# 1_POWER.net
KiCad netlist of a schematic drawn in Altium Designer
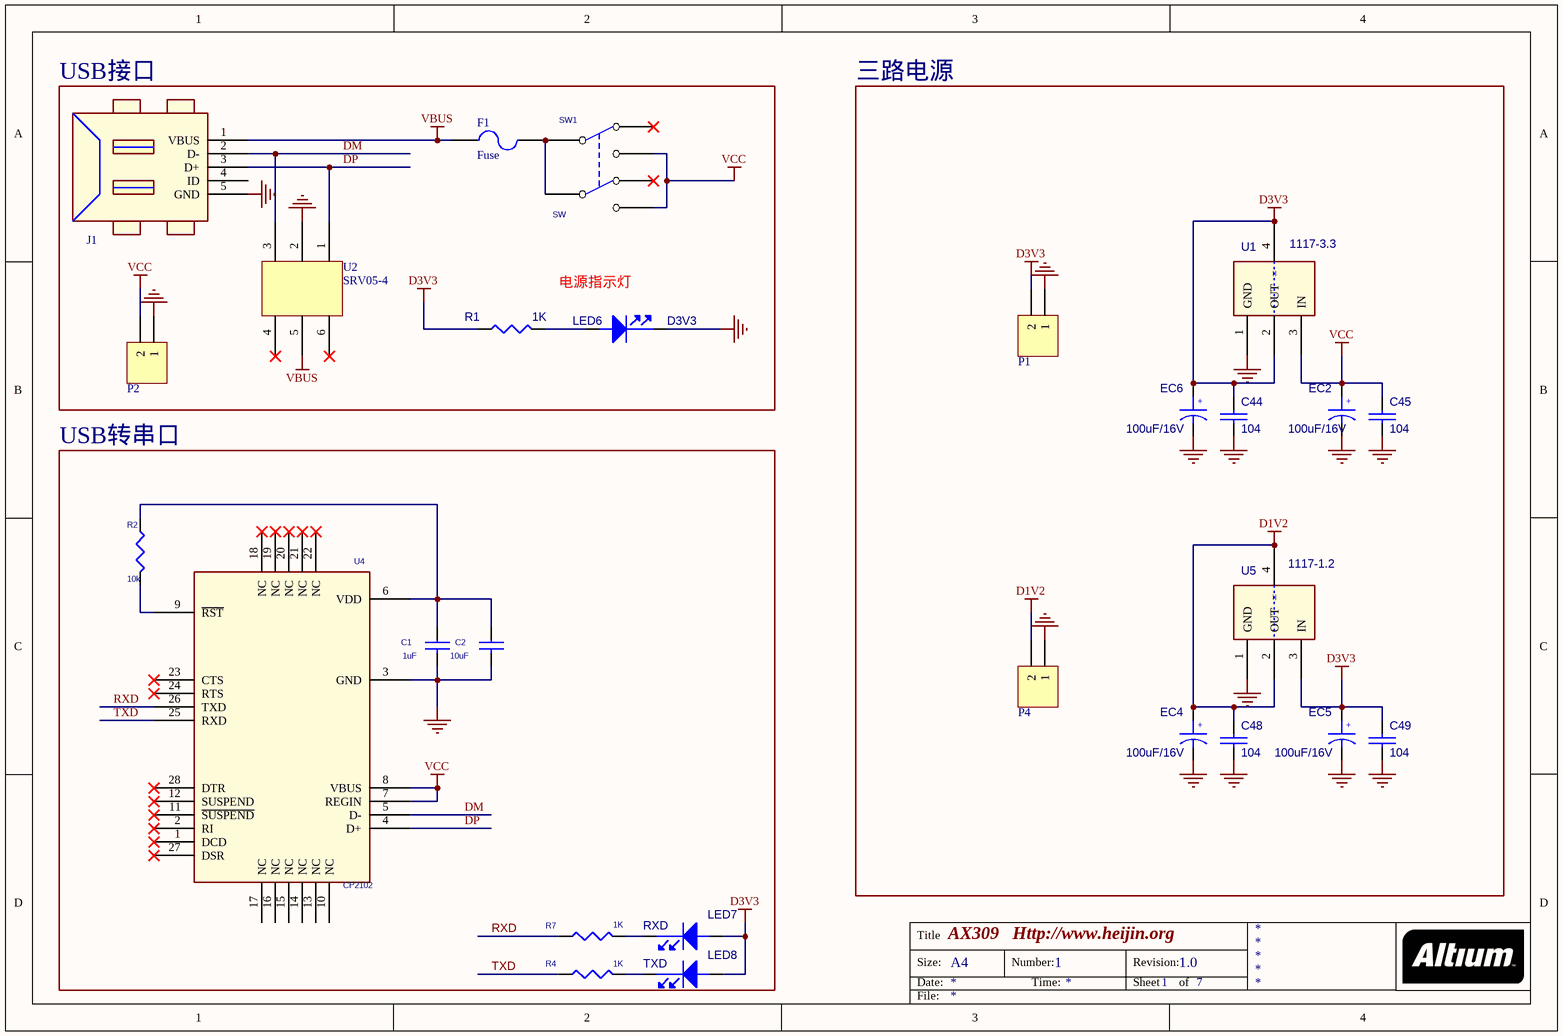
[diagram p0: 1_POWER.SchDoc]

(export (version "E")
  (design (tool "Eeschema 10.0.6"))
  (components
    (comp (ref "C1") (value "1uF") (libsource (lib "*") (part "CAP NP_Dup2")))
    (comp (ref "C2") (value "10uF") (libsource (lib "*") (part "CAP NP_Dup2")))
    (comp (ref "C44") (value "104") (libsource (lib "*") (part "C_Dup4")))
    (comp (ref "C45") (value "104") (libsource (lib "*") (part "C_Dup4")))
    (comp (ref "C48") (value "104") (libsource (lib "*") (part "C_Dup4")))
    (comp (ref "C49") (value "104") (libsource (lib "*") (part "C_Dup4")))
    (comp (ref "EC2") (value "100uF/16V") (libsource (lib "*") (part "EC")))
    (comp (ref "EC4") (value "100uF/16V") (libsource (lib "*") (part "EC")))
    (comp (ref "EC5") (value "100uF/16V") (libsource (lib "*") (part "EC")))
    (comp (ref "EC6") (value "100uF/16V") (libsource (lib "*") (part "EC")))
    (comp (ref "F1")
      (value "Fuse")
      (footprint "wfj_pcb:1206")
      (fields (field (name "PUBLISHER") "Altium Limited"))
      (libsource (lib "Miscellaneous Devices") (part "Fuse 2"))
    )
    (comp (ref "J1") (value "EC2") (footprint "MINIUSBB") (libsource (lib "*") (part "MiniUSBB")))
    (comp (ref "LED6") (value "D3V3") (footprint "LEDSO") (libsource (lib "*") (part "LED_Dup1")))
    (comp (ref "LED7") (value "RXD") (footprint "LEDSO") (libsource (lib "*") (part "LED")))
    (comp (ref "LED8") (value "TXD") (footprint "LEDSO") (libsource (lib "*") (part "LED")))
    (comp (ref "P1")
      (value "3.3V")
      (footprint "HDR1X2")
      (description "Header, 2-Pin")
      (fields (field (name "PUBLISHER") "Altium Limited"))
      (libsource (lib "Miscellaneous Connectors") (part "Header 2"))
    )
    (comp (ref "P2")
      (value "5V")
      (footprint "HDR1X2")
      (description "Header, 2-Pin")
      (fields (field (name "PUBLISHER") "Altium Limited"))
      (libsource (lib "Miscellaneous Connectors") (part "Header 2"))
    )
    (comp (ref "P4")
      (value "1.2V")
      (footprint "HDR1X2")
      (description "Header, 2-Pin")
      (fields (field (name "PUBLISHER") "Altium Limited"))
      (libsource (lib "Miscellaneous Connectors") (part "Header 2"))
    )
    (comp (ref "R1") (value "1K") (footprint "0603") (libsource (lib "*") (part "R")))
    (comp (ref "R2") (value "10k") (libsource (lib "*") (part "RESISTOR")))
    (comp (ref "R4") (value "1K") (footprint "0603") (libsource (lib "*") (part "R_Dup3")))
    (comp (ref "R7") (value "1K") (footprint "0603") (libsource (lib "*") (part "R_Dup3")))
    (comp (ref "SW1") (value "SW") (libsource (lib "*") (part "SW KEY-DPDT")))
    (comp (ref "U1") (value "1117-3.3") (footprint "SOT223") (libsource (lib "*") (part "1117-3.3")))
    (comp (ref "U2")
      (value "SRV05-4")
      (footprint "wfj_pcb:SOT23-6")
      (libsource (lib "heijin") (part "SRV05-4"))
    )
    (comp (ref "U4") (value "CP2102") (libsource (lib "*") (part "CP2102_0")))
    (comp (ref "U5") (value "1117-1.2") (footprint "SOT223") (libsource (lib "*") (part "1117-3.3")))
  )
  (nets
    (net (code "1") (name "/DM") (class "Default")
      (node (ref "J1") (pin "2") (pinfunction "D-_2") (pintype "passive"))
      (node (ref "U2") (pin "3") (pinfunction "3_3") (pintype "passive"))
      (node (ref "U4") (pin "5") (pinfunction "D-_5") (pintype "passive"))
    )
    (net (code "2") (name "/DP") (class "Default")
      (node (ref "J1") (pin "3") (pinfunction "D+_3") (pintype "passive"))
      (node (ref "U2") (pin "1") (pinfunction "1_1") (pintype "passive"))
      (node (ref "U4") (pin "4") (pinfunction "D+_4") (pintype "passive"))
    )
    (net (code "3") (name "/RXD") (class "Default")
      (node (ref "R7") (pin "1") (pinfunction "1_1") (pintype "passive"))
      (node (ref "U4") (pin "26") (pinfunction "TXD_26") (pintype "passive"))
    )
    (net (code "4") (name "/TXD") (class "Default")
      (node (ref "R4") (pin "1") (pinfunction "1_1") (pintype "passive"))
      (node (ref "U4") (pin "25") (pinfunction "RXD_25") (pintype "passive"))
    )
    (net (code "5") (name "D1V2") (class "Default")
      (node (ref "C48") (pin "1") (pinfunction "1_1") (pintype "passive"))
      (node (ref "EC4") (pin "1") (pinfunction "1_1") (pintype "passive"))
      (node (ref "P4") (pin "2") (pinfunction "2_2") (pintype "passive"))
      (node (ref "U5") (pin "2") (pinfunction "OUT_2") (pintype "passive"))
      (node (ref "U5") (pin "4") (pinfunction "=_4") (pintype "passive"))
    )
    (net (code "6") (name "D3V3") (class "Default")
      (node (ref "C44") (pin "1") (pinfunction "1_1") (pintype "passive"))
      (node (ref "C49") (pin "1") (pinfunction "1_1") (pintype "passive"))
      (node (ref "EC5") (pin "1") (pinfunction "1_1") (pintype "passive"))
      (node (ref "EC6") (pin "1") (pinfunction "1_1") (pintype "passive"))
      (node (ref "LED7") (pin "1") (pinfunction "ANODE_1") (pintype "passive"))
      (node (ref "LED8") (pin "1") (pinfunction "ANODE_1") (pintype "passive"))
      (node (ref "P1") (pin "2") (pinfunction "2_2") (pintype "passive"))
      (node (ref "R1") (pin "1") (pinfunction "1_1") (pintype "passive"))
      (node (ref "U1") (pin "2") (pinfunction "OUT_2") (pintype "passive"))
      (node (ref "U1") (pin "4") (pinfunction "=_4") (pintype "passive"))
      (node (ref "U5") (pin "3") (pinfunction "IN_3") (pintype "passive"))
    )
    (net (code "7") (name "GND") (class "Default")
      (node (ref "C1") (pin "2") (pinfunction "2_2") (pintype "passive"))
      (node (ref "C2") (pin "2") (pinfunction "2_2") (pintype "passive"))
      (node (ref "C44") (pin "2") (pinfunction "2_2") (pintype "passive"))
      (node (ref "C45") (pin "2") (pinfunction "2_2") (pintype "passive"))
      (node (ref "C48") (pin "2") (pinfunction "2_2") (pintype "passive"))
      (node (ref "C49") (pin "2") (pinfunction "2_2") (pintype "passive"))
      (node (ref "EC2") (pin "2") (pinfunction "2_2") (pintype "passive"))
      (node (ref "EC4") (pin "2") (pinfunction "2_2") (pintype "passive"))
      (node (ref "EC5") (pin "2") (pinfunction "2_2") (pintype "passive"))
      (node (ref "EC6") (pin "2") (pinfunction "2_2") (pintype "passive"))
      (node (ref "J1") (pin "5") (pinfunction "GND_5") (pintype "passive"))
      (node (ref "LED6") (pin "2") (pinfunction "CATHODE_2") (pintype "passive"))
      (node (ref "P1") (pin "1") (pinfunction "1_1") (pintype "passive"))
      (node (ref "P2") (pin "1") (pinfunction "1_1") (pintype "passive"))
      (node (ref "P4") (pin "1") (pinfunction "1_1") (pintype "passive"))
      (node (ref "U1") (pin "1") (pinfunction "GND_1") (pintype "passive"))
      (node (ref "U2") (pin "2") (pinfunction "2_2") (pintype "passive"))
      (node (ref "U4") (pin "3") (pinfunction "GND_3") (pintype "power_in"))
      (node (ref "U5") (pin "1") (pinfunction "GND_1") (pintype "passive"))
    )
    (net (code "8") (name "Net-(LED6-ANODE)") (class "Default")
      (node (ref "LED6") (pin "1") (pinfunction "ANODE_1") (pintype "passive"))
      (node (ref "R1") (pin "2") (pinfunction "2_2") (pintype "passive"))
    )
    (net (code "9") (name "Net-(LED7-CATHODE)") (class "Default")
      (node (ref "LED7") (pin "2") (pinfunction "CATHODE_2") (pintype "passive"))
      (node (ref "R7") (pin "2") (pinfunction "2_2") (pintype "passive"))
    )
    (net (code "10") (name "Net-(LED8-CATHODE)") (class "Default")
      (node (ref "LED8") (pin "2") (pinfunction "CATHODE_2") (pintype "passive"))
      (node (ref "R4") (pin "2") (pinfunction "2_2") (pintype "passive"))
    )
    (net (code "11") (name "Net-(SW1-COMMON1)") (class "Default")
      (node (ref "F1") (pin "2") (pinfunction "2_2") (pintype "passive"))
      (node (ref "SW1") (pin "2") (pinfunction "COMMON1_2") (pintype "passive"))
      (node (ref "SW1") (pin "5") (pinfunction "COMMON2_5") (pintype "passive"))
    )
    (net (code "12") (name "Net-(U4-VDD)") (class "Default")
      (node (ref "C1") (pin "1") (pinfunction "1_1") (pintype "passive"))
      (node (ref "C2") (pin "1") (pinfunction "1_1") (pintype "passive"))
      (node (ref "R2") (pin "2") (pinfunction "2_2") (pintype "passive"))
      (node (ref "U4") (pin "6") (pinfunction "VDD_6") (pintype "power_in"))
    )
    (net (code "13") (name "Net-(U4-~{RST})") (class "Default")
      (node (ref "R2") (pin "1") (pinfunction "1_1") (pintype "passive"))
      (node (ref "U4") (pin "9") (pinfunction "~{RST}_9") (pintype "passive"))
    )
    (net (code "14") (name "VBUS") (class "Default")
      (node (ref "F1") (pin "1") (pinfunction "1_1") (pintype "passive"))
      (node (ref "J1") (pin "1") (pinfunction "VBUS_1") (pintype "passive"))
      (node (ref "U2") (pin "5") (pinfunction "5_5") (pintype "passive"))
    )
    (net (code "15") (name "VCC") (class "Default")
      (node (ref "C45") (pin "1") (pinfunction "1_1") (pintype "passive"))
      (node (ref "EC2") (pin "1") (pinfunction "1_1") (pintype "passive"))
      (node (ref "P2") (pin "2") (pinfunction "2_2") (pintype "passive"))
      (node (ref "SW1") (pin "3") (pinfunction "NO1_3") (pintype "passive"))
      (node (ref "SW1") (pin "6") (pinfunction "NO2_6") (pintype "passive"))
      (node (ref "U1") (pin "3") (pinfunction "IN_3") (pintype "passive"))
      (node (ref "U4") (pin "7") (pinfunction "REGIN_7") (pintype "passive"))
      (node (ref "U4") (pin "8") (pinfunction "VBUS_8") (pintype "passive"))
    )
    (net (code "16") (name "unconnected-(J1-ID-Pad4)") (class "Default")
      (node (ref "J1") (pin "4") (pinfunction "ID_4") (pintype "passive"))
    )
    (net (code "17") (name "unconnected-(SW1-NC1-Pad1)") (class "Default")
      (node (ref "SW1") (pin "1") (pinfunction "NC1_1") (pintype "passive+no_connect"))
    )
    (net (code "18") (name "unconnected-(SW1-NC2-Pad4)") (class "Default")
      (node (ref "SW1") (pin "4") (pinfunction "NC2_4") (pintype "passive+no_connect"))
    )
    (net (code "19") (name "unconnected-(U2-Pad4)") (class "Default")
      (node (ref "U2") (pin "4") (pinfunction "4_4") (pintype "passive+no_connect"))
    )
    (net (code "20") (name "unconnected-(U2-Pad6)") (class "Default")
      (node (ref "U2") (pin "6") (pinfunction "6_6") (pintype "passive+no_connect"))
    )
    (net (code "21") (name "unconnected-(U4-CTS-Pad23)") (class "Default")
      (node (ref "U4") (pin "23") (pinfunction "CTS_23") (pintype "passive+no_connect"))
    )
    (net (code "22") (name "unconnected-(U4-DCD-Pad1)") (class "Default")
      (node (ref "U4") (pin "1") (pinfunction "DCD_1") (pintype "passive+no_connect"))
    )
    (net (code "23") (name "unconnected-(U4-DSR-Pad27)") (class "Default")
      (node (ref "U4") (pin "27") (pinfunction "DSR_27") (pintype "passive+no_connect"))
    )
    (net (code "24") (name "unconnected-(U4-DTR-Pad28)") (class "Default")
      (node (ref "U4") (pin "28") (pinfunction "DTR_28") (pintype "passive+no_connect"))
    )
    (net (code "25") (name "unconnected-(U4-NC-Pad10)") (class "Default")
      (node (ref "U4") (pin "10") (pinfunction "NC_10") (pintype "passive"))
    )
    (net (code "26") (name "unconnected-(U4-NC-Pad13)") (class "Default")
      (node (ref "U4") (pin "13") (pinfunction "NC_13") (pintype "passive"))
    )
    (net (code "27") (name "unconnected-(U4-NC-Pad14)") (class "Default")
      (node (ref "U4") (pin "14") (pinfunction "NC_14") (pintype "passive"))
    )
    (net (code "28") (name "unconnected-(U4-NC-Pad15)") (class "Default")
      (node (ref "U4") (pin "15") (pinfunction "NC_15") (pintype "passive"))
    )
    (net (code "29") (name "unconnected-(U4-NC-Pad16)") (class "Default")
      (node (ref "U4") (pin "16") (pinfunction "NC_16") (pintype "passive"))
    )
    (net (code "30") (name "unconnected-(U4-NC-Pad17)") (class "Default")
      (node (ref "U4") (pin "17") (pinfunction "NC_17") (pintype "passive"))
    )
    (net (code "31") (name "unconnected-(U4-NC-Pad18)") (class "Default")
      (node (ref "U4") (pin "18") (pinfunction "NC_18") (pintype "passive+no_connect"))
    )
    (net (code "32") (name "unconnected-(U4-NC-Pad19)") (class "Default")
      (node (ref "U4") (pin "19") (pinfunction "NC_19") (pintype "passive+no_connect"))
    )
    (net (code "33") (name "unconnected-(U4-NC-Pad20)") (class "Default")
      (node (ref "U4") (pin "20") (pinfunction "NC_20") (pintype "passive+no_connect"))
    )
    (net (code "34") (name "unconnected-(U4-NC-Pad21)") (class "Default")
      (node (ref "U4") (pin "21") (pinfunction "NC_21") (pintype "passive+no_connect"))
    )
    (net (code "35") (name "unconnected-(U4-NC-Pad22)") (class "Default")
      (node (ref "U4") (pin "22") (pinfunction "NC_22") (pintype "passive+no_connect"))
    )
    (net (code "36") (name "unconnected-(U4-RI-Pad2)") (class "Default")
      (node (ref "U4") (pin "2") (pinfunction "RI_2") (pintype "passive+no_connect"))
    )
    (net (code "37") (name "unconnected-(U4-RTS-Pad24)") (class "Default")
      (node (ref "U4") (pin "24") (pinfunction "RTS_24") (pintype "passive+no_connect"))
    )
    (net (code "38") (name "unconnected-(U4-SUSPEND-Pad12)") (class "Default")
      (node (ref "U4") (pin "12") (pinfunction "SUSPEND_12") (pintype "passive+no_connect"))
    )
    (net (code "39") (name "unconnected-(U4-~{SUSPEND}-Pad11)") (class "Default")
      (node (ref "U4") (pin "11") (pinfunction "~{SUSPEND}_11") (pintype "passive+no_connect"))
    )
  )
)
